# Current_meas.net
KiCad netlist of a schematic drawn in Altium Designer
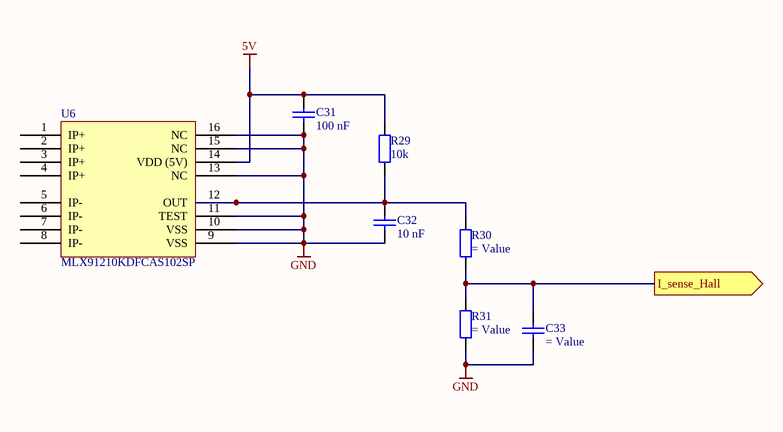
[diagram p0: Current_meas.SchDoc]

(export (version "E")
  (design (tool "Eeschema 10.0.6"))
  (components
    (comp (ref "C31") (value "100 nF") (footprint "0805_C") (libsource (lib "PJ") (part "CAP 0805")))
    (comp (ref "C32") (value "10 nF") (footprint "0805_C") (libsource (lib "PJ") (part "CAP 0805")))
    (comp (ref "C33") (value "~") (footprint "0805_C") (libsource (lib "PJ") (part "CAP 0805")))
    (comp (ref "R29") (value "10k") (libsource (lib "PJ") (part "RES 0805")))
    (comp (ref "R30") (value "~") (libsource (lib "PJ") (part "RES 0805")))
    (comp (ref "R31") (value "~") (libsource (lib "PJ") (part "RES 0805")))
    (comp (ref "U6")
      (value "MLX91210KDFCAS102SP")
      (footprint "SO-16Wide")
      (libsource (lib "PJ") (part "MLX91210KDFCAS102SP"))
    )
  )
  (nets
    (net (code "1") (name "/I_sense_Hall") (class "Default")
      (node (ref "C33") (pin "1") (pinfunction "1_1") (pintype "passive"))
      (node (ref "R30") (pin "1") (pinfunction "1_1") (pintype "passive"))
      (node (ref "R31") (pin "2") (pinfunction "2_2") (pintype "passive"))
    )
    (net (code "2") (name "5V") (class "Default")
      (node (ref "C31") (pin "1") (pinfunction "1_1") (pintype "passive"))
      (node (ref "R29") (pin "2") (pinfunction "2_2") (pintype "passive"))
      (node (ref "U6") (pin "14") (pinfunction "VDD_(5V)_14") (pintype "passive"))
    )
    (net (code "3") (name "GND") (class "Default")
      (node (ref "C31") (pin "2") (pinfunction "2_2") (pintype "passive"))
      (node (ref "C32") (pin "2") (pinfunction "2_2") (pintype "passive"))
      (node (ref "C33") (pin "2") (pinfunction "2_2") (pintype "passive"))
      (node (ref "R31") (pin "1") (pinfunction "1_1") (pintype "passive"))
      (node (ref "U6") (pin "10") (pinfunction "VSS_10") (pintype "passive"))
      (node (ref "U6") (pin "11") (pinfunction "TEST_11") (pintype "passive"))
      (node (ref "U6") (pin "13") (pinfunction "NC_13") (pintype "passive"))
      (node (ref "U6") (pin "15") (pinfunction "NC_15") (pintype "passive"))
      (node (ref "U6") (pin "16") (pinfunction "NC_16") (pintype "passive"))
      (node (ref "U6") (pin "9") (pinfunction "VSS_9") (pintype "passive"))
    )
    (net (code "4") (name "Net-(U6-OUT)") (class "Default")
      (node (ref "C32") (pin "1") (pinfunction "1_1") (pintype "passive"))
      (node (ref "R29") (pin "1") (pinfunction "1_1") (pintype "passive"))
      (node (ref "R30") (pin "2") (pinfunction "2_2") (pintype "passive"))
      (node (ref "U6") (pin "12") (pinfunction "OUT_12") (pintype "passive"))
    )
    (net (code "5") (name "unconnected-(U6-IP+-Pad1)") (class "Default")
      (node (ref "U6") (pin "1") (pinfunction "IP+_1") (pintype "passive"))
    )
    (net (code "6") (name "unconnected-(U6-IP+-Pad2)") (class "Default")
      (node (ref "U6") (pin "2") (pinfunction "IP+_2") (pintype "passive"))
    )
    (net (code "7") (name "unconnected-(U6-IP+-Pad3)") (class "Default")
      (node (ref "U6") (pin "3") (pinfunction "IP+_3") (pintype "passive"))
    )
    (net (code "8") (name "unconnected-(U6-IP+-Pad4)") (class "Default")
      (node (ref "U6") (pin "4") (pinfunction "IP+_4") (pintype "passive"))
    )
    (net (code "9") (name "unconnected-(U6-IP--Pad5)") (class "Default")
      (node (ref "U6") (pin "5") (pinfunction "IP-_5") (pintype "passive"))
    )
    (net (code "10") (name "unconnected-(U6-IP--Pad6)") (class "Default")
      (node (ref "U6") (pin "6") (pinfunction "IP-_6") (pintype "passive"))
    )
    (net (code "11") (name "unconnected-(U6-IP--Pad7)") (class "Default")
      (node (ref "U6") (pin "7") (pinfunction "IP-_7") (pintype "passive"))
    )
    (net (code "12") (name "unconnected-(U6-IP--Pad8)") (class "Default")
      (node (ref "U6") (pin "8") (pinfunction "IP-_8") (pintype "passive"))
    )
  )
)
